# Drimp_Quadcopter.net
KiCad netlist of a schematic drawn in Altium Designer
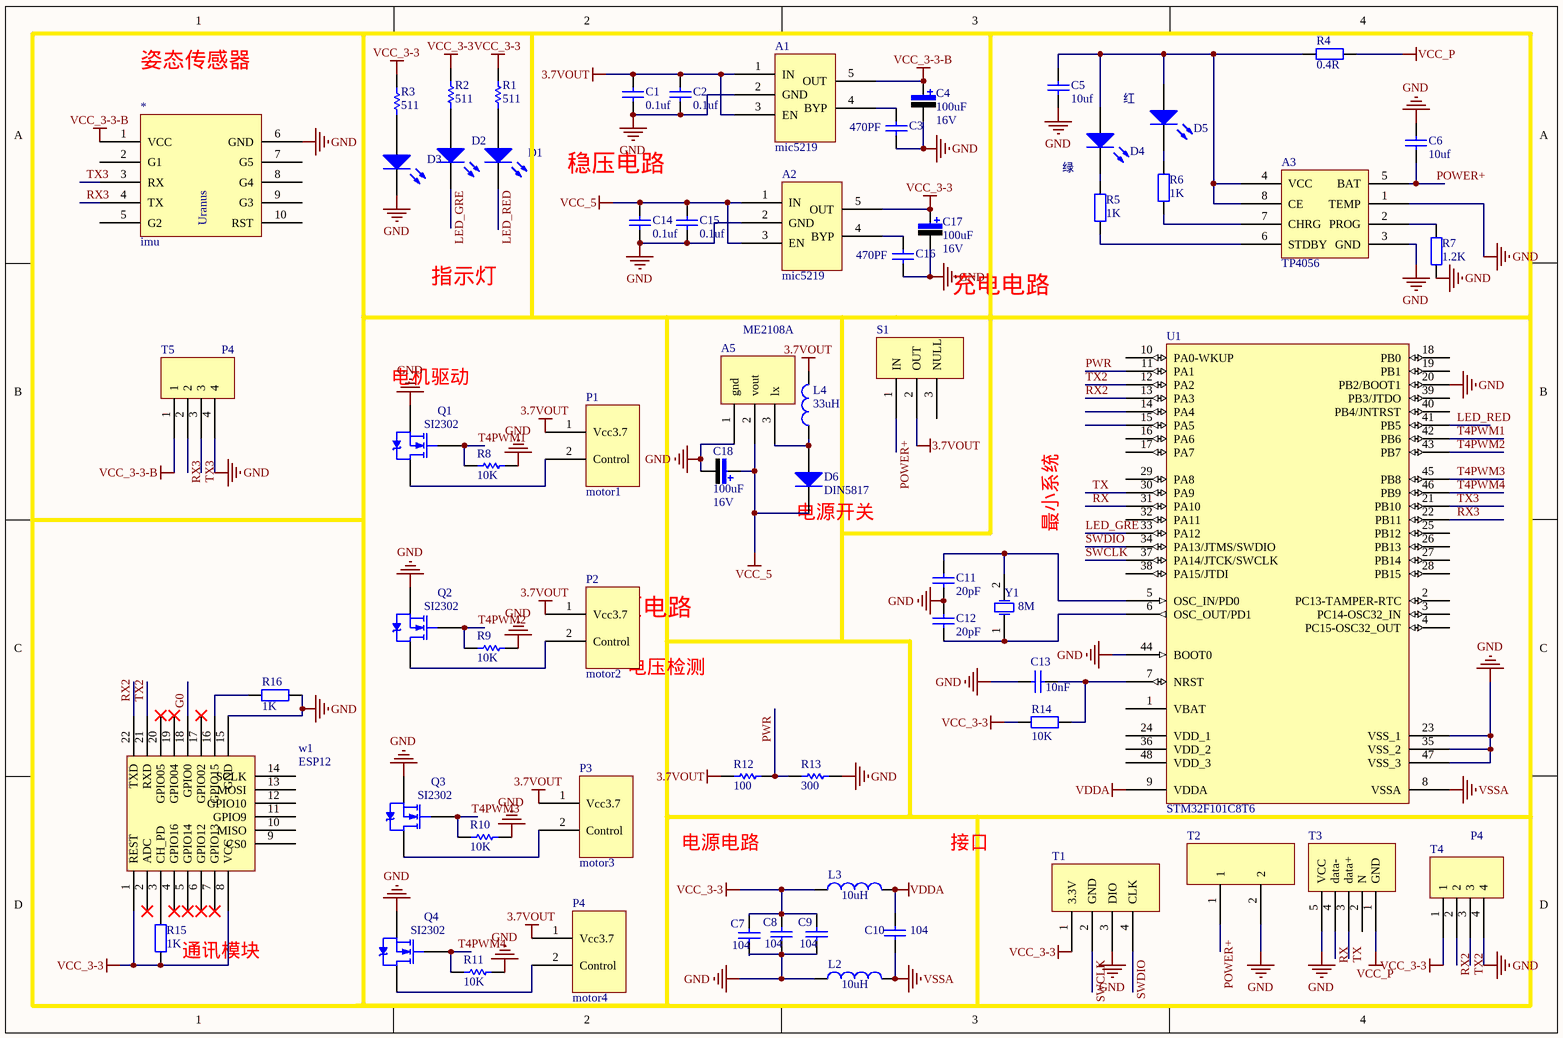
[diagram p0: Drimp_Quadcopter.SchDoc]

(export (version "E")
  (design (tool "Eeschema 10.0.6"))
  (components
    (comp (ref "*") (value "imu") (footprint "HI219M") (libsource (lib "Schlib1") (part "imu")))
    (comp (ref "A1")
      (value "mic5219")
      (footprint "SOT23-5")
      (description "低压差转3.3V")
      (libsource (lib "My") (part "mic5219"))
    )
    (comp (ref "A2")
      (value "mic5219")
      (footprint "SOT23-5")
      (description "低压差转3.3V")
      (libsource (lib "My") (part "mic5219"))
    )
    (comp (ref "A3") (value "TP4056") (footprint "SOP8") (libsource (lib "My") (part "TP4056")))
    (comp (ref "A5") (value "ME2108A") (footprint "SOT-89_M") (libsource (lib "My") (part "bl8530")))
    (comp (ref "C1")
      (value "0.1uf")
      (footprint "C-RAD-0603")
      (description "无极性电容")
      (fields (field (name "Comment") "Cap") (field (name "PUBLISHER") "Altium Limited"))
      (libsource (lib "Fszhang") (part "Cap"))
    )
    (comp (ref "C2")
      (value "0.1uf")
      (footprint "C-RAD-0603")
      (description "无极性电容")
      (fields (field (name "Comment") "Cap") (field (name "PUBLISHER") "Altium Limited"))
      (libsource (lib "Fszhang") (part "Cap"))
    )
    (comp (ref "C3")
      (value "470PF")
      (footprint "C-RAD-0603")
      (description "无极性电容")
      (fields (field (name "Comment") "Cap") (field (name "PUBLISHER") "Altium Limited"))
      (libsource (lib "Fszhang") (part "Cap"))
    )
    (comp (ref "C4")
      (value "100uF")
      (footprint "CAP-6032")
      (description "极性电解电容")
      (fields
        (field (name "VOL") "16V")
        (field (name "Comment") "Cap Pol")
        (field (name "PUBLISHER") "Altium Limited")
      )
      (libsource (lib "") (part "Cap Pol_1"))
    )
    (comp (ref "C5")
      (value "10uf")
      (footprint "C-RAD-0603")
      (description "无极性电容")
      (fields (field (name "Comment") "Cap") (field (name "PUBLISHER") "Altium Limited"))
      (libsource (lib "Fszhang") (part "Cap"))
    )
    (comp (ref "C6")
      (value "10uf")
      (footprint "C-RAD-0603")
      (description "无极性电容")
      (fields (field (name "Comment") "Cap") (field (name "PUBLISHER") "Altium Limited"))
      (libsource (lib "Fszhang") (part "Cap"))
    )
    (comp (ref "C7")
      (value "104")
      (footprint "0603-N-CAP")
      (description "Capacitor")
      (fields (field (name "Comment") "Cap") (field (name "PUBLISHER") "Altium Limited"))
      (libsource (lib "Miscellaneous Devices") (part "Cap"))
    )
    (comp (ref "C8")
      (value "104")
      (footprint "0603-N-CAP")
      (description "Capacitor")
      (fields (field (name "Comment") "Cap") (field (name "PUBLISHER") "Altium Limited"))
      (libsource (lib "Miscellaneous Devices") (part "Cap"))
    )
    (comp (ref "C9")
      (value "104")
      (footprint "0603-N-CAP")
      (description "Capacitor")
      (fields (field (name "Comment") "Cap") (field (name "PUBLISHER") "Altium Limited"))
      (libsource (lib "Miscellaneous Devices") (part "Cap"))
    )
    (comp (ref "C10")
      (value "104")
      (footprint "0603-N-CAP")
      (description "Capacitor")
      (fields (field (name "Comment") "Cap") (field (name "PUBLISHER") "Altium Limited"))
      (libsource (lib "Miscellaneous Devices") (part "Cap"))
    )
    (comp (ref "C11")
      (value "20pF")
      (footprint "0603-N-CAP")
      (description "Capacitor")
      (fields (field (name "Comment") "Cap") (field (name "PUBLISHER") "Altium Limited"))
      (libsource (lib "Miscellaneous Devices") (part "Cap"))
    )
    (comp (ref "C12")
      (value "20pF")
      (footprint "0603-N-CAP")
      (description "Capacitor")
      (fields (field (name "Comment") "Cap") (field (name "PUBLISHER") "Altium Limited"))
      (libsource (lib "Miscellaneous Devices") (part "Cap"))
    )
    (comp (ref "C13")
      (value "10nF")
      (footprint "0603-N-CAP")
      (description "Capacitor")
      (fields (field (name "Comment") "Cap") (field (name "PUBLISHER") "Altium Limited"))
      (libsource (lib "Miscellaneous Devices") (part "Cap"))
    )
    (comp (ref "C14")
      (value "0.1uf")
      (footprint "C-RAD-0603")
      (description "无极性电容")
      (fields (field (name "Comment") "Cap") (field (name "PUBLISHER") "Altium Limited"))
      (libsource (lib "Fszhang") (part "Cap"))
    )
    (comp (ref "C15")
      (value "0.1uf")
      (footprint "C-RAD-0603")
      (description "无极性电容")
      (fields (field (name "Comment") "Cap") (field (name "PUBLISHER") "Altium Limited"))
      (libsource (lib "Fszhang") (part "Cap"))
    )
    (comp (ref "C16")
      (value "470PF")
      (footprint "C-RAD-0603")
      (description "无极性电容")
      (fields (field (name "Comment") "Cap") (field (name "PUBLISHER") "Altium Limited"))
      (libsource (lib "Fszhang") (part "Cap"))
    )
    (comp (ref "C17")
      (value "100uF")
      (footprint "CAP-6032")
      (description "极性电解电容")
      (fields
        (field (name "VOL") "16V")
        (field (name "Comment") "Cap Pol")
        (field (name "PUBLISHER") "Altium Limited")
      )
      (libsource (lib "") (part "Cap Pol_1"))
    )
    (comp (ref "C18")
      (value "100uF")
      (footprint "CAP-6032")
      (description "极性电解电容")
      (fields
        (field (name "VOL") "16V")
        (field (name "Comment") "Cap Pol")
        (field (name "PUBLISHER") "Altium Limited")
      )
      (libsource (lib "Fszhang") (part "Cap Pol"))
    )
    (comp (ref "D1")
      (value "D2")
      (footprint "6-0805_N")
      (description "Typical BLUE SiC LED")
      (fields (field (name "PUBLISHER") "Altium Limited"))
      (libsource (lib "Miscellaneous Devices") (part "LED3"))
    )
    (comp (ref "D2")
      (value "D2")
      (footprint "6-0805_N")
      (description "Typical BLUE SiC LED")
      (fields (field (name "PUBLISHER") "Altium Limited"))
      (libsource (lib "Miscellaneous Devices") (part "LED3"))
    )
    (comp (ref "D3")
      (value "D2")
      (footprint "6-0805_N")
      (description "Typical BLUE SiC LED")
      (fields (field (name "PUBLISHER") "Altium Limited"))
      (libsource (lib "Miscellaneous Devices") (part "LED3"))
    )
    (comp (ref "D4")
      (value "LED0")
      (footprint "LED0805G")
      (description "发光二极管")
      (fields (field (name "PUBLISHER") "Altium Limited"))
      (libsource (lib "Fszhang") (part "LED0"))
    )
    (comp (ref "D5")
      (value "LED0")
      (footprint "LED0805R")
      (description "发光二极管")
      (fields (field (name "PUBLISHER") "Altium Limited"))
      (libsource (lib "Fszhang") (part "LED0"))
    )
    (comp (ref "D6")
      (value "Diode")
      (footprint "DIODE-SMA")
      (description "二极管")
      (fields (field (name "TYPE") "DIN5817") (field (name "PUBLISHER") "Altium Limited"))
      (libsource (lib "Fszhang") (part "Diode"))
    )
    (comp (ref "L2")
      (value "10uH")
      (footprint "0603-N - res")
      (description "Inductor")
      (fields (field (name "PUBLISHER") "Altium Limited"))
      (libsource (lib "Miscellaneous Devices") (part "Inductor"))
    )
    (comp (ref "L3")
      (value "10uH")
      (footprint "0603-N - res")
      (description "Inductor")
      (fields (field (name "PUBLISHER") "Altium Limited"))
      (libsource (lib "Miscellaneous Devices") (part "Inductor"))
    )
    (comp (ref "L4")
      (value "33uH")
      (footprint "CD54NP")
      (description "电感")
      (fields (field (name "Comment") "Inductor") (field (name "PUBLISHER") "Altium Limited"))
      (libsource (lib "Fszhang") (part "Inductor"))
    )
    (comp (ref "P1")
      (value "motor1")
      (footprint "P2-T-1.25")
      (description "电机连接口")
      (libsource (lib "Schlib1") (part "motor"))
    )
    (comp (ref "P2")
      (value "motor2")
      (footprint "P2-T-1.25")
      (description "电机连接口")
      (libsource (lib "Schlib1") (part "motor"))
    )
    (comp (ref "P3")
      (value "motor3")
      (footprint "P2-T-1.25")
      (description "电机连接口")
      (libsource (lib "Schlib1") (part "motor"))
    )
    (comp (ref "P4")
      (value "motor4")
      (footprint "P2-T-1.25")
      (description "电机连接口")
      (libsource (lib "Schlib1") (part "motor"))
    )
    (comp (ref "Q1")
      (value "SI2302")
      (footprint "SOT-23_M")
      (description "HEXFET Power MOSFET")
      (fields (field (name "PUBLISHER") "Altium Limited"))
      (libsource (lib "IR Discrete MOSFET - Power") (part "IRLML2402"))
    )
    (comp (ref "Q2")
      (value "SI2302")
      (footprint "SOT-23_M")
      (description "HEXFET Power MOSFET")
      (fields (field (name "PUBLISHER") "Altium Limited"))
      (libsource (lib "IR Discrete MOSFET - Power") (part "IRLML2402"))
    )
    (comp (ref "Q3")
      (value "SI2302")
      (footprint "SOT-23_M")
      (description "HEXFET Power MOSFET")
      (fields (field (name "PUBLISHER") "Altium Limited"))
      (libsource (lib "IR Discrete MOSFET - Power") (part "IRLML2402"))
    )
    (comp (ref "Q4")
      (value "SI2302")
      (footprint "SOT-23_M")
      (description "HEXFET Power MOSFET")
      (fields (field (name "PUBLISHER") "Altium Limited"))
      (libsource (lib "IR Discrete MOSFET - Power") (part "IRLML2402"))
    )
    (comp (ref "R1")
      (value "511")
      (footprint "0603-N - res")
      (description "Resistor")
      (fields (field (name "Comment") "Res1") (field (name "PUBLISHER") "Altium Limited"))
      (libsource (lib "Miscellaneous Devices") (part "Res1"))
    )
    (comp (ref "R2")
      (value "511")
      (footprint "0603-N - res")
      (description "Resistor")
      (fields (field (name "Comment") "Res1") (field (name "PUBLISHER") "Altium Limited"))
      (libsource (lib "Miscellaneous Devices") (part "Res1"))
    )
    (comp (ref "R3")
      (value "511")
      (footprint "0603-N - res")
      (description "Resistor")
      (fields (field (name "Comment") "Res1") (field (name "PUBLISHER") "Altium Limited"))
      (libsource (lib "Miscellaneous Devices") (part "Res1"))
    )
    (comp (ref "R4")
      (value "0.4R")
      (footprint "1206")
      (description "贴片电阻")
      (fields (field (name "Comment") "Res1") (field (name "PUBLISHER") "Altium Limited"))
      (libsource (lib "") (part "Res1_1"))
    )
    (comp (ref "R5")
      (value "1K")
      (footprint "0603-1")
      (description "贴片电阻")
      (fields (field (name "Comment") "Res1") (field (name "PUBLISHER") "Altium Limited"))
      (libsource (lib "Fszhang") (part "Res1"))
    )
    (comp (ref "R6")
      (value "1K")
      (footprint "0603-1")
      (description "贴片电阻")
      (fields (field (name "Comment") "Res1") (field (name "PUBLISHER") "Altium Limited"))
      (libsource (lib "Fszhang") (part "Res1"))
    )
    (comp (ref "R7")
      (value "1.2K")
      (footprint "0603-1")
      (description "贴片电阻")
      (fields (field (name "Comment") "Res1") (field (name "PUBLISHER") "Altium Limited"))
      (libsource (lib "Fszhang") (part "Res1"))
    )
    (comp (ref "R8")
      (value "10K")
      (footprint "0603-N - res")
      (description "Resistor")
      (fields (field (name "Comment") "Res1") (field (name "PUBLISHER") "Altium Limited"))
      (libsource (lib "Miscellaneous Devices") (part "Res1"))
    )
    (comp (ref "R9")
      (value "10K")
      (footprint "0603-N - res")
      (description "Resistor")
      (fields (field (name "Comment") "Res1") (field (name "PUBLISHER") "Altium Limited"))
      (libsource (lib "Miscellaneous Devices") (part "Res1"))
    )
    (comp (ref "R10")
      (value "10K")
      (footprint "0603-N - res")
      (description "Resistor")
      (fields (field (name "Comment") "Res1") (field (name "PUBLISHER") "Altium Limited"))
      (libsource (lib "Miscellaneous Devices") (part "Res1"))
    )
    (comp (ref "R11")
      (value "10K")
      (footprint "0603-N - res")
      (description "Resistor")
      (fields (field (name "Comment") "Res1") (field (name "PUBLISHER") "Altium Limited"))
      (libsource (lib "Miscellaneous Devices") (part "Res1"))
    )
    (comp (ref "R12")
      (value "100")
      (footprint "0603-N - res")
      (description "Resistor")
      (fields (field (name "Comment") "Res1") (field (name "PUBLISHER") "Altium Limited"))
      (libsource (lib "Miscellaneous Devices") (part "Res1"))
    )
    (comp (ref "R13")
      (value "300")
      (footprint "0603-N - res")
      (description "Resistor")
      (fields (field (name "Comment") "Res1") (field (name "PUBLISHER") "Altium Limited"))
      (libsource (lib "Miscellaneous Devices") (part "Res1"))
    )
    (comp (ref "R14")
      (value "10K")
      (footprint "0603-N - res")
      (description "Resistor")
      (fields (field (name "Comment") "Res2") (field (name "PUBLISHER") "Altium Limited"))
      (libsource (lib "") (part "Res2_1"))
    )
    (comp (ref "R15")
      (value "1K")
      (footprint "0603-N - res")
      (description "Resistor")
      (fields (field (name "Comment") "Res2") (field (name "PUBLISHER") "Altium Limited"))
      (libsource (lib "") (part "Res2_2"))
    )
    (comp (ref "R16")
      (value "1K")
      (footprint "0603-N - res")
      (description "Resistor")
      (fields (field (name "Comment") "Res2") (field (name "PUBLISHER") "Altium Limited"))
      (libsource (lib "Miscellaneous Devices") (part "Res2"))
    )
    (comp (ref "S1") (value "switch") (footprint "拨动开关") (libsource (lib "Schlib1") (part "switch")))
    (comp (ref "T1")
      (value "SW_download")
      (footprint "P4_1.25")
      (libsource (lib "Schlib1") (part "SW_download"))
    )
    (comp (ref "T2") (value "P2") (footprint "P2") (libsource (lib "My") (part "P2")))
    (comp (ref "T3") (value "mini usb") (footprint "USB_micro_2") (libsource (lib "My") (part "mini usb")))
    (comp (ref "T4") (value "P4") (footprint "P4_1.25") (libsource (lib "My") (part "P4")))
    (comp (ref "T5") (value "P4") (footprint "P4_1.25") (libsource (lib "My") (part "P4")))
    (comp (ref "U1")
      (value "STM32F101C8T6")
      (footprint "LQFP48_N")
      (description "STM32 ARM-based 32-bit MCU with 64 Kbytes Flash, 48-pin LQFP, Industrial Temperature")
      (fields (field (name "PUBLISHER") "Altium Limited"))
      (libsource (lib "ST Microcontroller 32-Bit STM32") (part "STM32F101C8T6"))
    )
    (comp (ref "w1") (value "ESP12") (footprint "ESP_12_F") (libsource (lib "My") (part "ESP12")))
    (comp (ref "Y1")
      (value "8M")
      (footprint "5032_")
      (description "Crystal Oscillator")
      (fields (field (name "PUBLISHER") "Altium Limited"))
      (libsource (lib "Miscellaneous Devices") (part "XTAL"))
    )
  )
  (nets
    (net (code "1") (name "/G0") (class "Default")
      (node (ref "w1") (pin "18") (pinfunction "GPIO0_18") (pintype "passive"))
    )
    (net (code "2") (name "/LED_GRE") (class "Default")
      (node (ref "D2") (pin "2") (pinfunction "K_2") (pintype "passive"))
      (node (ref "U1") (pin "33") (pinfunction "PA12_33") (pintype "bidirectional"))
    )
    (net (code "3") (name "/LED_RED") (class "Default")
      (node (ref "D1") (pin "2") (pinfunction "K_2") (pintype "passive"))
      (node (ref "U1") (pin "41") (pinfunction "PB5_41") (pintype "bidirectional"))
    )
    (net (code "4") (name "/POWER+") (class "Default")
      (node (ref "A3") (pin "5") (pinfunction "BAT_5") (pintype "passive"))
      (node (ref "C6") (pin "1") (pinfunction "1_1") (pintype "passive"))
      (node (ref "S1") (pin "1") (pinfunction "IN_1") (pintype "passive"))
      (node (ref "T2") (pin "1") (pinfunction "1_1") (pintype "passive"))
    )
    (net (code "5") (name "/PWR") (class "Default")
      (node (ref "R12") (pin "2") (pinfunction "2_2") (pintype "passive"))
      (node (ref "R13") (pin "1") (pinfunction "1_1") (pintype "passive"))
      (node (ref "U1") (pin "11") (pinfunction "PA1_11") (pintype "bidirectional"))
    )
    (net (code "6") (name "/RX") (class "Default")
      (node (ref "T3") (pin "4") (pinfunction "data-_4") (pintype "passive"))
      (node (ref "U1") (pin "31") (pinfunction "PA10_31") (pintype "bidirectional"))
    )
    (net (code "7") (name "/RX2") (class "Default")
      (node (ref "T4") (pin "2") (pinfunction "2_2") (pintype "passive"))
      (node (ref "U1") (pin "13") (pinfunction "PA3_13") (pintype "bidirectional"))
      (node (ref "w1") (pin "22") (pinfunction "TXD_22") (pintype "passive"))
    )
    (net (code "8") (name "/RX3") (class "Default")
      (node (ref "*") (pin "4") (pinfunction "TX_4") (pintype "passive"))
      (node (ref "T5") (pin "2") (pinfunction "2_2") (pintype "passive"))
      (node (ref "U1") (pin "22") (pinfunction "PB11_22") (pintype "bidirectional"))
    )
    (net (code "9") (name "/SWCLK") (class "Default")
      (node (ref "T1") (pin "2") (pinfunction "GND_2") (pintype "passive"))
      (node (ref "U1") (pin "37") (pinfunction "PA14/JTCK/SWCLK_37") (pintype "bidirectional"))
    )
    (net (code "10") (name "/SWDIO") (class "Default")
      (node (ref "T1") (pin "4") (pinfunction "CLK_4") (pintype "passive"))
      (node (ref "U1") (pin "34") (pinfunction "PA13/JTMS/SWDIO_34") (pintype "bidirectional"))
    )
    (net (code "11") (name "/T4PWM1") (class "Default")
      (node (ref "Q1") (pin "1") (pinfunction "G_1") (pintype "passive"))
      (node (ref "R8") (pin "1") (pinfunction "1_1") (pintype "passive"))
      (node (ref "U1") (pin "42") (pinfunction "PB6_42") (pintype "bidirectional"))
    )
    (net (code "12") (name "/T4PWM2") (class "Default")
      (node (ref "Q2") (pin "1") (pinfunction "G_1") (pintype "passive"))
      (node (ref "R9") (pin "1") (pinfunction "1_1") (pintype "passive"))
      (node (ref "U1") (pin "43") (pinfunction "PB7_43") (pintype "bidirectional"))
    )
    (net (code "13") (name "/T4PWM3") (class "Default")
      (node (ref "Q3") (pin "1") (pinfunction "G_1") (pintype "passive"))
      (node (ref "R10") (pin "1") (pinfunction "1_1") (pintype "passive"))
      (node (ref "U1") (pin "45") (pinfunction "PB8_45") (pintype "bidirectional"))
    )
    (net (code "14") (name "/T4PWM4") (class "Default")
      (node (ref "Q4") (pin "1") (pinfunction "G_1") (pintype "passive"))
      (node (ref "R11") (pin "1") (pinfunction "1_1") (pintype "passive"))
      (node (ref "U1") (pin "46") (pinfunction "PB9_46") (pintype "bidirectional"))
    )
    (net (code "15") (name "/TX") (class "Default")
      (node (ref "T3") (pin "3") (pinfunction "data+_3") (pintype "passive"))
      (node (ref "U1") (pin "30") (pinfunction "PA9_30") (pintype "bidirectional"))
    )
    (net (code "16") (name "/TX2") (class "Default")
      (node (ref "T4") (pin "3") (pinfunction "3_3") (pintype "passive"))
      (node (ref "U1") (pin "12") (pinfunction "PA2_12") (pintype "bidirectional"))
      (node (ref "w1") (pin "21") (pinfunction "RXD_21") (pintype "passive"))
    )
    (net (code "17") (name "/TX3") (class "Default")
      (node (ref "*") (pin "3") (pinfunction "RX_3") (pintype "passive"))
      (node (ref "T5") (pin "3") (pinfunction "3_3") (pintype "passive"))
      (node (ref "U1") (pin "21") (pinfunction "PB10_21") (pintype "bidirectional"))
    )
    (net (code "18") (name "3.7VOUT") (class "Default")
      (node (ref "A1") (pin "1") (pinfunction "IN_1") (pintype "passive"))
      (node (ref "A1") (pin "3") (pinfunction "EN_3") (pintype "passive"))
      (node (ref "C1") (pin "2") (pinfunction "2_2") (pintype "passive"))
      (node (ref "C2") (pin "2") (pinfunction "2_2") (pintype "passive"))
      (node (ref "L4") (pin "2") (pinfunction "2_2") (pintype "passive"))
      (node (ref "P1") (pin "1") (pinfunction "Vcc3.7_1") (pintype "passive"))
      (node (ref "P2") (pin "1") (pinfunction "Vcc3.7_1") (pintype "passive"))
      (node (ref "P3") (pin "1") (pinfunction "Vcc3.7_1") (pintype "passive"))
      (node (ref "P4") (pin "1") (pinfunction "Vcc3.7_1") (pintype "passive"))
      (node (ref "R12") (pin "1") (pinfunction "1_1") (pintype "passive"))
      (node (ref "S1") (pin "2") (pinfunction "OUT_2") (pintype "passive"))
    )
    (net (code "19") (name "GND") (class "Default")
      (node (ref "*") (pin "6") (pinfunction "GND_6") (pintype "passive"))
      (node (ref "A1") (pin "2") (pinfunction "GND_2") (pintype "passive"))
      (node (ref "A2") (pin "2") (pinfunction "GND_2") (pintype "passive"))
      (node (ref "A3") (pin "1") (pinfunction "TEMP_1") (pintype "passive"))
      (node (ref "A3") (pin "3") (pinfunction "GND_3") (pintype "passive"))
      (node (ref "A5") (pin "1") (pinfunction "gnd_1") (pintype "passive"))
      (node (ref "C1") (pin "1") (pinfunction "1_1") (pintype "passive"))
      (node (ref "C11") (pin "1") (pinfunction "1_1") (pintype "passive"))
      (node (ref "C12") (pin "2") (pinfunction "2_2") (pintype "passive"))
      (node (ref "C13") (pin "1") (pinfunction "1_1") (pintype "passive"))
      (node (ref "C14") (pin "1") (pinfunction "1_1") (pintype "passive"))
      (node (ref "C15") (pin "1") (pinfunction "1_1") (pintype "passive"))
      (node (ref "C16") (pin "1") (pinfunction "1_1") (pintype "passive"))
      (node (ref "C17") (pin "2") (pinfunction "2_2") (pintype "passive"))
      (node (ref "C18") (pin "2") (pinfunction "2_2") (pintype "passive"))
      (node (ref "C2") (pin "1") (pinfunction "1_1") (pintype "passive"))
      (node (ref "C3") (pin "1") (pinfunction "1_1") (pintype "passive"))
      (node (ref "C4") (pin "2") (pinfunction "2_2") (pintype "passive"))
      (node (ref "C5") (pin "1") (pinfunction "1_1") (pintype "passive"))
      (node (ref "C6") (pin "2") (pinfunction "2_2") (pintype "passive"))
      (node (ref "C7") (pin "1") (pinfunction "1_1") (pintype "passive"))
      (node (ref "C8") (pin "1") (pinfunction "1_1") (pintype "passive"))
      (node (ref "C9") (pin "1") (pinfunction "1_1") (pintype "passive"))
      (node (ref "D3") (pin "2") (pinfunction "K_2") (pintype "passive"))
      (node (ref "L2") (pin "1") (pinfunction "1_1") (pintype "passive"))
      (node (ref "Q1") (pin "2") (pinfunction "S_2") (pintype "passive"))
      (node (ref "Q2") (pin "2") (pinfunction "S_2") (pintype "passive"))
      (node (ref "Q3") (pin "2") (pinfunction "S_2") (pintype "passive"))
      (node (ref "Q4") (pin "2") (pinfunction "S_2") (pintype "passive"))
      (node (ref "R10") (pin "2") (pinfunction "2_2") (pintype "passive"))
      (node (ref "R11") (pin "2") (pinfunction "2_2") (pintype "passive"))
      (node (ref "R13") (pin "2") (pinfunction "2_2") (pintype "passive"))
      (node (ref "R16") (pin "1") (pinfunction "1_1") (pintype "passive"))
      (node (ref "R7") (pin "2") (pinfunction "2_2") (pintype "passive"))
      (node (ref "R8") (pin "2") (pinfunction "2_2") (pintype "passive"))
      (node (ref "R9") (pin "2") (pinfunction "2_2") (pintype "passive"))
      (node (ref "T1") (pin "3") (pinfunction "DIO_3") (pintype "passive"))
      (node (ref "T2") (pin "2") (pinfunction "2_2") (pintype "passive"))
      (node (ref "T3") (pin "5") (pinfunction "VCC_5") (pintype "passive"))
      (node (ref "T4") (pin "4") (pinfunction "4_4") (pintype "passive"))
      (node (ref "T5") (pin "4") (pinfunction "4_4") (pintype "passive"))
      (node (ref "U1") (pin "20") (pinfunction "PB2/BOOT1_20") (pintype "bidirectional"))
      (node (ref "U1") (pin "23") (pinfunction "VSS_1_23") (pintype "power_in"))
      (node (ref "U1") (pin "35") (pinfunction "VSS_2_35") (pintype "power_in"))
      (node (ref "U1") (pin "44") (pinfunction "BOOT0_44") (pintype "input"))
      (node (ref "U1") (pin "47") (pinfunction "VSS_3_47") (pintype "power_in"))
      (node (ref "w1") (pin "15") (pinfunction "GND_15") (pintype "passive"))
    )
    (net (code "20") (name "Net-(A1-BYP)") (class "Default")
      (node (ref "A1") (pin "4") (pinfunction "BYP_4") (pintype "passive"))
      (node (ref "C3") (pin "2") (pinfunction "2_2") (pintype "passive"))
    )
    (net (code "21") (name "Net-(A2-BYP)") (class "Default")
      (node (ref "A2") (pin "4") (pinfunction "BYP_4") (pintype "passive"))
      (node (ref "C16") (pin "2") (pinfunction "2_2") (pintype "passive"))
    )
    (net (code "22") (name "Net-(A3-CE)") (class "Default")
      (node (ref "A3") (pin "4") (pinfunction "VCC_4") (pintype "passive"))
      (node (ref "A3") (pin "8") (pinfunction "CE_8") (pintype "passive"))
      (node (ref "C5") (pin "2") (pinfunction "2_2") (pintype "passive"))
      (node (ref "D4") (pin "1") (pinfunction "A_1") (pintype "passive"))
      (node (ref "D5") (pin "1") (pinfunction "A_1") (pintype "passive"))
      (node (ref "R4") (pin "1") (pinfunction "1_1") (pintype "passive"))
    )
    (net (code "23") (name "Net-(A3-CHRG)") (class "Default")
      (node (ref "A3") (pin "7") (pinfunction "CHRG_7") (pintype "passive"))
      (node (ref "R6") (pin "2") (pinfunction "2_2") (pintype "passive"))
    )
    (net (code "24") (name "Net-(A3-PROG)") (class "Default")
      (node (ref "A3") (pin "2") (pinfunction "PROG_2") (pintype "passive"))
      (node (ref "R7") (pin "1") (pinfunction "1_1") (pintype "passive"))
    )
    (net (code "25") (name "Net-(A3-STDBY)") (class "Default")
      (node (ref "A3") (pin "6") (pinfunction "STDBY_6") (pintype "passive"))
      (node (ref "R5") (pin "2") (pinfunction "2_2") (pintype "passive"))
    )
    (net (code "26") (name "Net-(A5-lx)") (class "Default")
      (node (ref "A5") (pin "3") (pinfunction "lx_3") (pintype "passive"))
      (node (ref "D6") (pin "1") (pinfunction "A_1") (pintype "passive"))
      (node (ref "L4") (pin "1") (pinfunction "1_1") (pintype "passive"))
    )
    (net (code "27") (name "Net-(D1-A)") (class "Default")
      (node (ref "D1") (pin "1") (pinfunction "A_1") (pintype "passive"))
      (node (ref "R1") (pin "1") (pinfunction "1_1") (pintype "passive"))
    )
    (net (code "28") (name "Net-(D2-A)") (class "Default")
      (node (ref "D2") (pin "1") (pinfunction "A_1") (pintype "passive"))
      (node (ref "R2") (pin "1") (pinfunction "1_1") (pintype "passive"))
    )
    (net (code "29") (name "Net-(D3-A)") (class "Default")
      (node (ref "D3") (pin "1") (pinfunction "A_1") (pintype "passive"))
      (node (ref "R3") (pin "1") (pinfunction "1_1") (pintype "passive"))
    )
    (net (code "30") (name "Net-(D4-K)") (class "Default")
      (node (ref "D4") (pin "2") (pinfunction "K_2") (pintype "passive"))
      (node (ref "R5") (pin "1") (pinfunction "1_1") (pintype "passive"))
    )
    (net (code "31") (name "Net-(D5-K)") (class "Default")
      (node (ref "D5") (pin "2") (pinfunction "K_2") (pintype "passive"))
      (node (ref "R6") (pin "1") (pinfunction "1_1") (pintype "passive"))
    )
    (net (code "32") (name "Net-(P1-Control)") (class "Default")
      (node (ref "P1") (pin "2") (pinfunction "Control_2") (pintype "passive"))
      (node (ref "Q1") (pin "3") (pinfunction "D_3") (pintype "passive"))
    )
    (net (code "33") (name "Net-(P2-Control)") (class "Default")
      (node (ref "P2") (pin "2") (pinfunction "Control_2") (pintype "passive"))
      (node (ref "Q2") (pin "3") (pinfunction "D_3") (pintype "passive"))
    )
    (net (code "34") (name "Net-(P3-Control)") (class "Default")
      (node (ref "P3") (pin "2") (pinfunction "Control_2") (pintype "passive"))
      (node (ref "Q3") (pin "3") (pinfunction "D_3") (pintype "passive"))
    )
    (net (code "35") (name "Net-(P4-Control)") (class "Default")
      (node (ref "P4") (pin "2") (pinfunction "Control_2") (pintype "passive"))
      (node (ref "Q4") (pin "3") (pinfunction "D_3") (pintype "passive"))
    )
    (net (code "36") (name "Net-(U1-NRST)") (class "Default")
      (node (ref "C13") (pin "2") (pinfunction "2_2") (pintype "passive"))
      (node (ref "R14") (pin "2") (pinfunction "2_2") (pintype "passive"))
      (node (ref "U1") (pin "7") (pinfunction "NRST_7") (pintype "bidirectional"))
    )
    (net (code "37") (name "Net-(U1-OSC_IN{slash}PD0)") (class "Default")
      (node (ref "C11") (pin "2") (pinfunction "2_2") (pintype "passive"))
      (node (ref "U1") (pin "5") (pinfunction "OSC_IN/PD0_5") (pintype "input"))
      (node (ref "Y1") (pin "2") (pinfunction "OSC2_2") (pintype "passive"))
    )
    (net (code "38") (name "Net-(U1-OSC_OUT{slash}PD1)") (class "Default")
      (node (ref "C12") (pin "1") (pinfunction "1_1") (pintype "passive"))
      (node (ref "U1") (pin "6") (pinfunction "OSC_OUT/PD1_6") (pintype "output"))
      (node (ref "Y1") (pin "1") (pinfunction "OSC1_1") (pintype "passive"))
    )
    (net (code "39") (name "Net-(w1-CH_PD)") (class "Default")
      (node (ref "R15") (pin "2") (pinfunction "2_2") (pintype "passive"))
      (node (ref "w1") (pin "3") (pinfunction "CH_PD_3") (pintype "passive"))
    )
    (net (code "40") (name "Net-(w1-GPIO15)") (class "Default")
      (node (ref "R16") (pin "2") (pinfunction "2_2") (pintype "passive"))
      (node (ref "w1") (pin "16") (pinfunction "GPIO15_16") (pintype "passive"))
    )
    (net (code "41") (name "VCC_3-3") (class "Default")
      (node (ref "A2") (pin "5") (pinfunction "OUT_5") (pintype "passive"))
      (node (ref "C17") (pin "1") (pinfunction "1_1") (pintype "passive"))
      (node (ref "C7") (pin "2") (pinfunction "2_2") (pintype "passive"))
      (node (ref "C8") (pin "2") (pinfunction "2_2") (pintype "passive"))
      (node (ref "C9") (pin "2") (pinfunction "2_2") (pintype "passive"))
      (node (ref "L3") (pin "1") (pinfunction "1_1") (pintype "passive"))
      (node (ref "R1") (pin "2") (pinfunction "2_2") (pintype "passive"))
      (node (ref "R14") (pin "1") (pinfunction "1_1") (pintype "passive"))
      (node (ref "R15") (pin "1") (pinfunction "1_1") (pintype "passive"))
      (node (ref "R2") (pin "2") (pinfunction "2_2") (pintype "passive"))
      (node (ref "R3") (pin "2") (pinfunction "2_2") (pintype "passive"))
      (node (ref "T1") (pin "1") (pinfunction "3.3V_1") (pintype "passive"))
      (node (ref "T4") (pin "1") (pinfunction "1_1") (pintype "passive"))
      (node (ref "w1") (pin "1") (pinfunction "REST_1") (pintype "passive"))
      (node (ref "w1") (pin "8") (pinfunction "VCC_8") (pintype "passive"))
    )
    (net (code "42") (name "VCC_3-3-B") (class "Default")
      (node (ref "*") (pin "1") (pinfunction "VCC_1") (pintype "passive"))
      (node (ref "A1") (pin "5") (pinfunction "OUT_5") (pintype "passive"))
      (node (ref "C4") (pin "1") (pinfunction "1_1") (pintype "passive"))
      (node (ref "T5") (pin "1") (pinfunction "1_1") (pintype "passive"))
    )
    (net (code "43") (name "VCC_5") (class "Default")
      (node (ref "A2") (pin "1") (pinfunction "IN_1") (pintype "passive"))
      (node (ref "A2") (pin "3") (pinfunction "EN_3") (pintype "passive"))
      (node (ref "A5") (pin "2") (pinfunction "vout_2") (pintype "passive"))
      (node (ref "C14") (pin "2") (pinfunction "2_2") (pintype "passive"))
      (node (ref "C15") (pin "2") (pinfunction "2_2") (pintype "passive"))
      (node (ref "C18") (pin "1") (pinfunction "1_1") (pintype "passive"))
      (node (ref "D6") (pin "2") (pinfunction "K_2") (pintype "passive"))
    )
    (net (code "44") (name "VCC_P") (class "Default")
      (node (ref "R4") (pin "2") (pinfunction "2_2") (pintype "passive"))
      (node (ref "T3") (pin "1") (pinfunction "GND_1") (pintype "passive"))
    )
    (net (code "45") (name "VDDA") (class "Default")
      (node (ref "C10") (pin "2") (pinfunction "2_2") (pintype "passive"))
      (node (ref "L3") (pin "2") (pinfunction "2_2") (pintype "passive"))
      (node (ref "U1") (pin "9") (pinfunction "VDDA_9") (pintype "power_in"))
    )
    (net (code "46") (name "VSSA") (class "Default")
      (node (ref "C10") (pin "1") (pinfunction "1_1") (pintype "passive"))
      (node (ref "L2") (pin "2") (pinfunction "2_2") (pintype "passive"))
      (node (ref "U1") (pin "8") (pinfunction "VSSA_8") (pintype "power_in"))
    )
    (net (code "47") (name "unconnected-(*-G1-Pad2)") (class "Default")
      (node (ref "*") (pin "2") (pinfunction "G1_2") (pintype "passive"))
    )
    (net (code "48") (name "unconnected-(*-G2-Pad5)") (class "Default")
      (node (ref "*") (pin "5") (pinfunction "G2_5") (pintype "passive"))
    )
    (net (code "49") (name "unconnected-(*-G3-Pad9)") (class "Default")
      (node (ref "*") (pin "9") (pinfunction "G3_9") (pintype "passive"))
    )
    (net (code "50") (name "unconnected-(*-G4-Pad8)") (class "Default")
      (node (ref "*") (pin "8") (pinfunction "G4_8") (pintype "passive"))
    )
    (net (code "51") (name "unconnected-(*-G5-Pad7)") (class "Default")
      (node (ref "*") (pin "7") (pinfunction "G5_7") (pintype "passive"))
    )
    (net (code "52") (name "unconnected-(*-RST-Pad10)") (class "Default")
      (node (ref "*") (pin "10") (pinfunction "RST_10") (pintype "passive"))
    )
    (net (code "53") (name "unconnected-(S1-NULL-Pad3)") (class "Default")
      (node (ref "S1") (pin "3") (pinfunction "NULL_3") (pintype "passive"))
    )
    (net (code "54") (name "unconnected-(T3-N-Pad2)") (class "Default")
      (node (ref "T3") (pin "2") (pinfunction "N_2") (pintype "passive"))
    )
    (net (code "55") (name "unconnected-(U1-PA0-WKUP-Pad10)") (class "Default")
      (node (ref "U1") (pin "10") (pinfunction "PA0-WKUP_10") (pintype "bidirectional"))
    )
    (net (code "56") (name "unconnected-(U1-PA4-Pad14)") (class "Default")
      (node (ref "U1") (pin "14") (pinfunction "PA4_14") (pintype "bidirectional"))
    )
    (net (code "57") (name "unconnected-(U1-PA5-Pad15)") (class "Default")
      (node (ref "U1") (pin "15") (pinfunction "PA5_15") (pintype "bidirectional"))
    )
    (net (code "58") (name "unconnected-(U1-PA6-Pad16)") (class "Default")
      (node (ref "U1") (pin "16") (pinfunction "PA6_16") (pintype "bidirectional"))
    )
    (net (code "59") (name "unconnected-(U1-PA7-Pad17)") (class "Default")
      (node (ref "U1") (pin "17") (pinfunction "PA7_17") (pintype "bidirectional"))
    )
    (net (code "60") (name "unconnected-(U1-PA8-Pad29)") (class "Default")
      (node (ref "U1") (pin "29") (pinfunction "PA8_29") (pintype "bidirectional"))
    )
    (net (code "61") (name "unconnected-(U1-PA11-Pad32)") (class "Default")
      (node (ref "U1") (pin "32") (pinfunction "PA11_32") (pintype "bidirectional"))
    )
    (net (code "62") (name "unconnected-(U1-PA15{slash}JTDI-Pad38)") (class "Default")
      (node (ref "U1") (pin "38") (pinfunction "PA15/JTDI_38") (pintype "bidirectional"))
    )
    (net (code "63") (name "unconnected-(U1-PB0-Pad18)") (class "Default")
      (node (ref "U1") (pin "18") (pinfunction "PB0_18") (pintype "bidirectional"))
    )
    (net (code "64") (name "unconnected-(U1-PB1-Pad19)") (class "Default")
      (node (ref "U1") (pin "19") (pinfunction "PB1_19") (pintype "bidirectional"))
    )
    (net (code "65") (name "unconnected-(U1-PB3{slash}JTDO-Pad39)") (class "Default")
      (node (ref "U1") (pin "39") (pinfunction "PB3/JTDO_39") (pintype "bidirectional"))
    )
    (net (code "66") (name "unconnected-(U1-PB4{slash}JNTRST-Pad40)") (class "Default")
      (node (ref "U1") (pin "40") (pinfunction "PB4/JNTRST_40") (pintype "bidirectional"))
    )
    (net (code "67") (name "unconnected-(U1-PB12-Pad25)") (class "Default")
      (node (ref "U1") (pin "25") (pinfunction "PB12_25") (pintype "bidirectional"))
    )
    (net (code "68") (name "unconnected-(U1-PB13-Pad26)") (class "Default")
      (node (ref "U1") (pin "26") (pinfunction "PB13_26") (pintype "bidirectional"))
    )
    (net (code "69") (name "unconnected-(U1-PB14-Pad27)") (class "Default")
      (node (ref "U1") (pin "27") (pinfunction "PB14_27") (pintype "bidirectional"))
    )
    (net (code "70") (name "unconnected-(U1-PB15-Pad28)") (class "Default")
      (node (ref "U1") (pin "28") (pinfunction "PB15_28") (pintype "bidirectional"))
    )
    (net (code "71") (name "unconnected-(U1-PC13-TAMPER-RTC-Pad2)") (class "Default")
      (node (ref "U1") (pin "2") (pinfunction "PC13-TAMPER-RTC_2") (pintype "bidirectional"))
    )
    (net (code "72") (name "unconnected-(U1-PC14-OSC32_IN-Pad3)") (class "Default")
      (node (ref "U1") (pin "3") (pinfunction "PC14-OSC32_IN_3") (pintype "bidirectional"))
    )
    (net (code "73") (name "unconnected-(U1-PC15-OSC32_OUT-Pad4)") (class "Default")
      (node (ref "U1") (pin "4") (pinfunction "PC15-OSC32_OUT_4") (pintype "bidirectional"))
    )
    (net (code "74") (name "unconnected-(U1-VBAT-Pad1)") (class "Default")
      (node (ref "U1") (pin "1") (pinfunction "VBAT_1") (pintype "power_in"))
    )
    (net (code "75") (name "unconnected-(U1-VDD_1-Pad24)") (class "Default")
      (node (ref "U1") (pin "24") (pinfunction "VDD_1_24") (pintype "power_in"))
    )
    (net (code "76") (name "unconnected-(U1-VDD_2-Pad36)") (class "Default")
      (node (ref "U1") (pin "36") (pinfunction "VDD_2_36") (pintype "power_in"))
    )
    (net (code "77") (name "unconnected-(U1-VDD_3-Pad48)") (class "Default")
      (node (ref "U1") (pin "48") (pinfunction "VDD_3_48") (pintype "power_in"))
    )
    (net (code "78") (name "unconnected-(w1-ADC-Pad2)") (class "Default")
      (node (ref "w1") (pin "2") (pinfunction "ADC_2") (pintype "passive+no_connect"))
    )
    (net (code "79") (name "unconnected-(w1-CS0-Pad9)") (class "Default")
      (node (ref "w1") (pin "9") (pinfunction "CS0_9") (pintype "passive"))
    )
    (net (code "80") (name "unconnected-(w1-GPIO02-Pad17)") (class "Default")
      (node (ref "w1") (pin "17") (pinfunction "GPIO02_17") (pintype "passive+no_connect"))
    )
    (net (code "81") (name "unconnected-(w1-GPIO04-Pad19)") (class "Default")
      (node (ref "w1") (pin "19") (pinfunction "GPIO04_19") (pintype "passive+no_connect"))
    )
    (net (code "82") (name "unconnected-(w1-GPIO05-Pad20)") (class "Default")
      (node (ref "w1") (pin "20") (pinfunction "GPIO05_20") (pintype "passive+no_connect"))
    )
    (net (code "83") (name "unconnected-(w1-GPIO9-Pad11)") (class "Default")
      (node (ref "w1") (pin "11") (pinfunction "GPIO9_11") (pintype "passive"))
    )
    (net (code "84") (name "unconnected-(w1-GPIO10-Pad12)") (class "Default")
      (node (ref "w1") (pin "12") (pinfunction "GPIO10_12") (pintype "passive"))
    )
    (net (code "85") (name "unconnected-(w1-GPIO12-Pad6)") (class "Default")
      (node (ref "w1") (pin "6") (pinfunction "GPIO12_6") (pintype "passive+no_connect"))
    )
    (net (code "86") (name "unconnected-(w1-GPIO13-Pad7)") (class "Default")
      (node (ref "w1") (pin "7") (pinfunction "GPIO13_7") (pintype "passive+no_connect"))
    )
    (net (code "87") (name "unconnected-(w1-GPIO14-Pad5)") (class "Default")
      (node (ref "w1") (pin "5") (pinfunction "GPIO14_5") (pintype "passive+no_connect"))
    )
    (net (code "88") (name "unconnected-(w1-GPIO16-Pad4)") (class "Default")
      (node (ref "w1") (pin "4") (pinfunction "GPIO16_4") (pintype "passive+no_connect"))
    )
    (net (code "89") (name "unconnected-(w1-MISO-Pad10)") (class "Default")
      (node (ref "w1") (pin "10") (pinfunction "MISO_10") (pintype "passive"))
    )
    (net (code "90") (name "unconnected-(w1-MOSI-Pad13)") (class "Default")
      (node (ref "w1") (pin "13") (pinfunction "MOSI_13") (pintype "passive"))
    )
    (net (code "91") (name "unconnected-(w1-SCLK-Pad14)") (class "Default")
      (node (ref "w1") (pin "14") (pinfunction "SCLK_14") (pintype "passive"))
    )
  )
)
